# Micro_SD_Card.net
KiCad netlist of a schematic drawn in Altium Designer
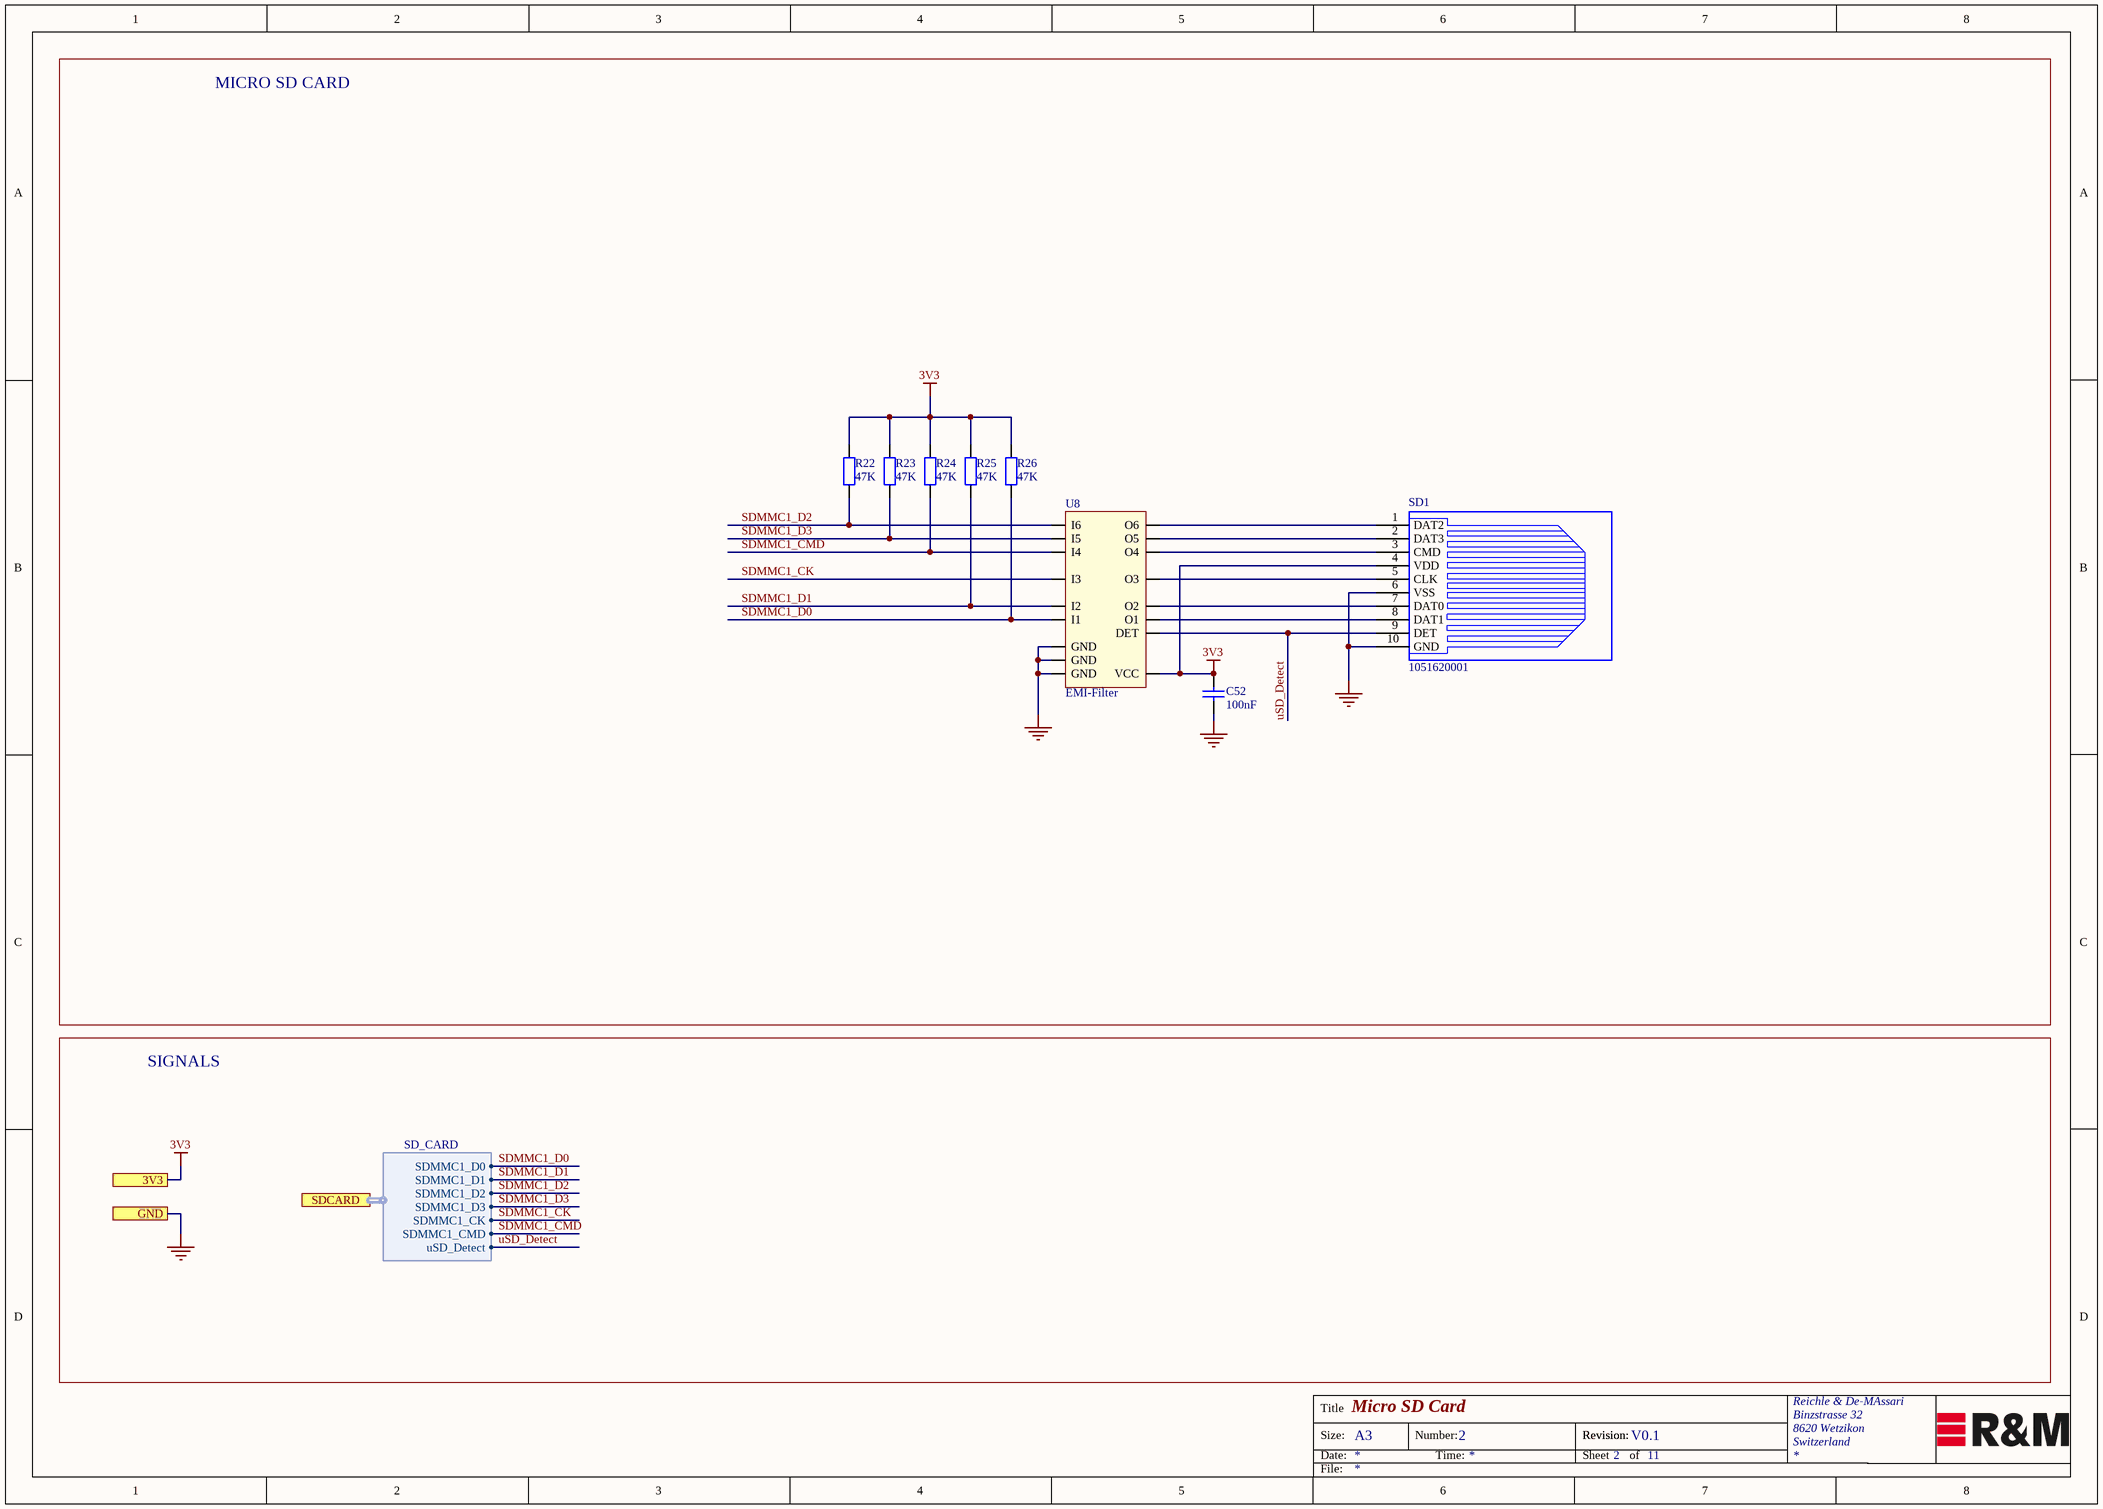
[diagram p0: Micro_SD_Card.SchDoc]

(export (version "E")
  (design (tool "Eeschema 10.0.6"))
  (components
    (comp (ref "C52")
      (value "100nF")
      (footprint "Ceramic Capacitor 0402 EIA")
      (description "0,1µF ±10% 10V Keramikkondensatoren X7R 0402 (1005 metrisch)")
      (fields (field (name "MANUFACTURER") "Samsung"))
      (libsource (lib "RDM_ALT_SCH") (part "Cap_100nF_0402_10V"))
    )
    (comp (ref "R22")
      (value "47K")
      (footprint "Resistor 0402 EIA")
      (fields
        (field (name "TOLERANCE") "5%")
        (field (name "POWER") "62.5mW")
        (field (name "MANUFACTURER") "TE Connectivity")
      )
      (libsource (lib "RDM_ALT_SCH") (part "Res_47K_0402"))
    )
    (comp (ref "R23")
      (value "47K")
      (footprint "Resistor 0402 EIA")
      (fields
        (field (name "TOLERANCE") "5%")
        (field (name "POWER") "62.5mW")
        (field (name "MANUFACTURER") "TE Connectivity")
      )
      (libsource (lib "RDM_ALT_SCH") (part "Res_47K_0402"))
    )
    (comp (ref "R24")
      (value "47K")
      (footprint "Resistor 0402 EIA")
      (fields
        (field (name "TOLERANCE") "5%")
        (field (name "POWER") "62.5mW")
        (field (name "MANUFACTURER") "TE Connectivity")
      )
      (libsource (lib "RDM_ALT_SCH") (part "Res_47K_0402"))
    )
    (comp (ref "R25")
      (value "47K")
      (footprint "Resistor 0402 EIA")
      (fields
        (field (name "TOLERANCE") "5%")
        (field (name "POWER") "62.5mW")
        (field (name "MANUFACTURER") "TE Connectivity")
      )
      (libsource (lib "RDM_ALT_SCH") (part "Res_47K_0402"))
    )
    (comp (ref "R26")
      (value "47K")
      (footprint "Resistor 0402 EIA")
      (fields
        (field (name "TOLERANCE") "5%")
        (field (name "POWER") "62.5mW")
        (field (name "MANUFACTURER") "TE Connectivity")
      )
      (libsource (lib "RDM_ALT_SCH") (part "Res_47K_0402"))
    )
    (comp (ref "SD1")
      (value "1051620001")
      (footprint "SD-105162-001")
      (description "Memory Card Connectors 1.45H MICRO SD HEADER WITH D/C PIN, Molex")
      (fields (field (name "MANUFACTURER") "Molex, LLC"))
      (libsource (lib "RDM_ALT_SCH") (part "CONN_MICRO_SD"))
    )
    (comp (ref "U8")
      (value "EMI-Filter")
      (footprint "WFBGA-17-Balls")
      (description "RLC EMI Filter 3rd Order Low Pass 6 Channel L = 1nH, C = 2.5pF 17-WFBGA, FCBGA")
      (fields (field (name "MANUFACTURER") "STMicroelectronics"))
      (libsource (lib "RDM_ALT_SCH") (part "EMI_Filter"))
    )
  )
  (nets
    (net (code "2") (name "/SDMMC1_CK") (class "Default")
      (node (ref "U8") (pin "I3") (pinfunction "I3_I3") (pintype "passive"))
    )
    (net (code "3") (name "/SDMMC1_CMD") (class "Default")
      (node (ref "R24") (pin "2") (pinfunction "2_2") (pintype "passive"))
      (node (ref "U8") (pin "I4") (pinfunction "I4_I4") (pintype "passive"))
    )
    (net (code "4") (name "/SDMMC1_D0") (class "Default")
      (node (ref "R26") (pin "2") (pinfunction "2_2") (pintype "passive"))
      (node (ref "U8") (pin "I1") (pinfunction "I1_I1") (pintype "passive"))
    )
    (net (code "5") (name "/SDMMC1_D1") (class "Default")
      (node (ref "R25") (pin "2") (pinfunction "2_2") (pintype "passive"))
      (node (ref "U8") (pin "I2") (pinfunction "I2_I2") (pintype "passive"))
    )
    (net (code "6") (name "/SDMMC1_D2") (class "Default")
      (node (ref "R22") (pin "2") (pinfunction "2_2") (pintype "passive"))
      (node (ref "U8") (pin "I6") (pinfunction "I6_I6") (pintype "passive"))
    )
    (net (code "7") (name "/SDMMC1_D3") (class "Default")
      (node (ref "R23") (pin "2") (pinfunction "2_2") (pintype "passive"))
      (node (ref "U8") (pin "I5") (pinfunction "I5_I5") (pintype "passive"))
    )
    (net (code "8") (name "/uSD_Detect") (class "Default")
      (node (ref "SD1") (pin "9") (pinfunction "DET_9") (pintype "passive"))
      (node (ref "U8") (pin "DET") (pinfunction "DET_DET") (pintype "passive"))
    )
    (net (code "10") (name "3V3") (class "Default")
      (node (ref "C52") (pin "2") (pinfunction "2_2") (pintype "passive"))
      (node (ref "R22") (pin "1") (pinfunction "1_1") (pintype "passive"))
      (node (ref "R23") (pin "1") (pinfunction "1_1") (pintype "passive"))
      (node (ref "R24") (pin "1") (pinfunction "1_1") (pintype "passive"))
      (node (ref "R25") (pin "1") (pinfunction "1_1") (pintype "passive"))
      (node (ref "R26") (pin "1") (pinfunction "1_1") (pintype "passive"))
      (node (ref "SD1") (pin "4") (pinfunction "VDD_4") (pintype "passive"))
      (node (ref "U8") (pin "VCC") (pinfunction "VCC_VCC") (pintype "passive"))
    )
    (net (code "11") (name "GND") (class "Default")
      (node (ref "C52") (pin "1") (pinfunction "1_1") (pintype "passive"))
      (node (ref "SD1") (pin "10") (pinfunction "GND_10") (pintype "passive"))
      (node (ref "SD1") (pin "6") (pinfunction "VSS_6") (pintype "passive"))
      (node (ref "U8") (pin "GND") (pinfunction "GND_GND") (pintype "passive"))
    )
    (net (code "12") (name "Net-(SD1-CLK)") (class "Default")
      (node (ref "SD1") (pin "5") (pinfunction "CLK_5") (pintype "passive"))
      (node (ref "U8") (pin "O3") (pinfunction "O3_O3") (pintype "passive"))
    )
    (net (code "13") (name "Net-(SD1-CMD)") (class "Default")
      (node (ref "SD1") (pin "3") (pinfunction "CMD_3") (pintype "passive"))
      (node (ref "U8") (pin "O4") (pinfunction "O4_O4") (pintype "passive"))
    )
    (net (code "14") (name "Net-(SD1-DAT0)") (class "Default")
      (node (ref "SD1") (pin "7") (pinfunction "DAT0_7") (pintype "passive"))
      (node (ref "U8") (pin "O2") (pinfunction "O2_O2") (pintype "passive"))
    )
    (net (code "15") (name "Net-(SD1-DAT1)") (class "Default")
      (node (ref "SD1") (pin "8") (pinfunction "DAT1_8") (pintype "passive"))
      (node (ref "U8") (pin "O1") (pinfunction "O1_O1") (pintype "passive"))
    )
    (net (code "16") (name "Net-(SD1-DAT2)") (class "Default")
      (node (ref "SD1") (pin "1") (pinfunction "DAT2_1") (pintype "passive"))
      (node (ref "U8") (pin "O6") (pinfunction "O6_O6") (pintype "passive"))
    )
    (net (code "17") (name "Net-(SD1-DAT3)") (class "Default")
      (node (ref "SD1") (pin "2") (pinfunction "DAT3_2") (pintype "passive"))
      (node (ref "U8") (pin "O5") (pinfunction "O5_O5") (pintype "passive"))
    )
  )
)
